# Motherboard_Connection.net
KiCad netlist of a schematic drawn in Altium Designer
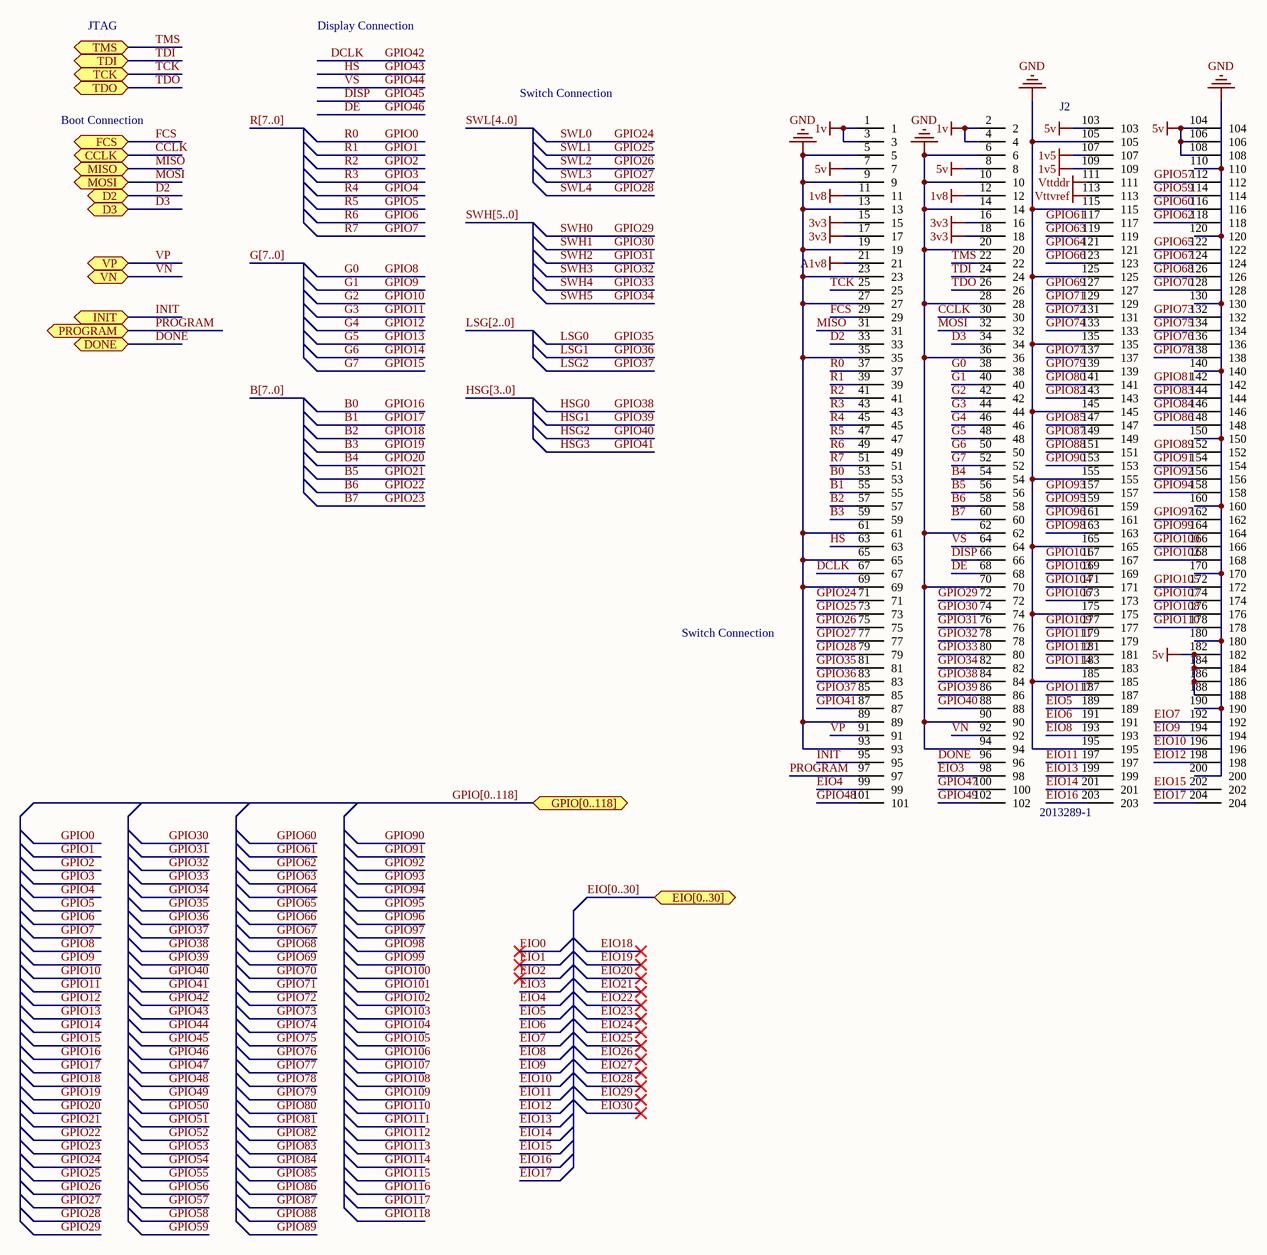
[diagram p0: Motherboard Connection.SchDoc]

(export (version "E")
  (design (tool "Eeschema 10.0.6"))
  (components
    (comp (ref "J2")
      (value "2013289-1")
      (footprint "DDR3 SODIMM Gold Finger")
      (description "204 Position 0.6 mm Pitch Right Angle Surface Mount Socket DIMM Connector")
      (fields (field (name "DIGI-KEY_PART_NUMBER") "A115021-ND") (field (name "MF") "TE Connectivity"))
      (libsource (lib "2020-09-26_17-27-19") (part "2013289-1"))
    )
  )
  (nets
    (net (code "2") (name "/CCLK") (class "Default")
      (node (ref "J2") (pin "30") (pinfunction "30_30") (pintype "passive"))
    )
    (net (code "3") (name "/D2") (class "Default")
      (node (ref "J2") (pin "33") (pinfunction "33_33") (pintype "passive"))
    )
    (net (code "4") (name "/D3") (class "Default")
      (node (ref "J2") (pin "34") (pinfunction "34_34") (pintype "passive"))
    )
    (net (code "5") (name "/DONE") (class "Default")
      (node (ref "J2") (pin "96") (pinfunction "96_96") (pintype "passive"))
    )
    (net (code "9") (name "/EIO3") (class "Default")
      (node (ref "J2") (pin "98") (pinfunction "98_98") (pintype "passive"))
    )
    (net (code "10") (name "/EIO4") (class "Default")
      (node (ref "J2") (pin "99") (pinfunction "99_99") (pintype "passive"))
    )
    (net (code "11") (name "/EIO5") (class "Default")
      (node (ref "J2") (pin "189") (pinfunction "189_189") (pintype "passive"))
    )
    (net (code "12") (name "/EIO6") (class "Default")
      (node (ref "J2") (pin "191") (pinfunction "191_191") (pintype "passive"))
    )
    (net (code "13") (name "/EIO7") (class "Default")
      (node (ref "J2") (pin "192") (pinfunction "192_192") (pintype "passive"))
    )
    (net (code "14") (name "/EIO8") (class "Default")
      (node (ref "J2") (pin "193") (pinfunction "193_193") (pintype "passive"))
    )
    (net (code "15") (name "/EIO9") (class "Default")
      (node (ref "J2") (pin "194") (pinfunction "194_194") (pintype "passive"))
    )
    (net (code "16") (name "/EIO10") (class "Default")
      (node (ref "J2") (pin "196") (pinfunction "196_196") (pintype "passive"))
    )
    (net (code "17") (name "/EIO11") (class "Default")
      (node (ref "J2") (pin "197") (pinfunction "197_197") (pintype "passive"))
    )
    (net (code "18") (name "/EIO12") (class "Default")
      (node (ref "J2") (pin "198") (pinfunction "198_198") (pintype "passive"))
    )
    (net (code "19") (name "/EIO13") (class "Default")
      (node (ref "J2") (pin "199") (pinfunction "199_199") (pintype "passive"))
    )
    (net (code "20") (name "/EIO14") (class "Default")
      (node (ref "J2") (pin "201") (pinfunction "201_201") (pintype "passive"))
    )
    (net (code "21") (name "/EIO15") (class "Default")
      (node (ref "J2") (pin "202") (pinfunction "202_202") (pintype "passive"))
    )
    (net (code "22") (name "/EIO16") (class "Default")
      (node (ref "J2") (pin "203") (pinfunction "203_203") (pintype "passive"))
    )
    (net (code "23") (name "/EIO17") (class "Default")
      (node (ref "J2") (pin "204") (pinfunction "204_204") (pintype "passive"))
    )
    (net (code "38") (name "/FCS") (class "Default")
      (node (ref "J2") (pin "29") (pinfunction "29_29") (pintype "passive"))
    )
    (net (code "39") (name "/GPIO0") (class "Default")
      (node (ref "J2") (pin "37") (pinfunction "37_37") (pintype "passive"))
    )
    (net (code "40") (name "/GPIO1") (class "Default")
      (node (ref "J2") (pin "39") (pinfunction "39_39") (pintype "passive"))
    )
    (net (code "41") (name "/GPIO2") (class "Default")
      (node (ref "J2") (pin "41") (pinfunction "41_41") (pintype "passive"))
    )
    (net (code "42") (name "/GPIO3") (class "Default")
      (node (ref "J2") (pin "43") (pinfunction "43_43") (pintype "passive"))
    )
    (net (code "43") (name "/GPIO4") (class "Default")
      (node (ref "J2") (pin "45") (pinfunction "45_45") (pintype "passive"))
    )
    (net (code "44") (name "/GPIO5") (class "Default")
      (node (ref "J2") (pin "47") (pinfunction "47_47") (pintype "passive"))
    )
    (net (code "45") (name "/GPIO6") (class "Default")
      (node (ref "J2") (pin "49") (pinfunction "49_49") (pintype "passive"))
    )
    (net (code "46") (name "/GPIO7") (class "Default")
      (node (ref "J2") (pin "51") (pinfunction "51_51") (pintype "passive"))
    )
    (net (code "47") (name "/GPIO8") (class "Default")
      (node (ref "J2") (pin "38") (pinfunction "38_38") (pintype "passive"))
    )
    (net (code "48") (name "/GPIO9") (class "Default")
      (node (ref "J2") (pin "40") (pinfunction "40_40") (pintype "passive"))
    )
    (net (code "49") (name "/GPIO10") (class "Default")
      (node (ref "J2") (pin "42") (pinfunction "42_42") (pintype "passive"))
    )
    (net (code "50") (name "/GPIO11") (class "Default")
      (node (ref "J2") (pin "44") (pinfunction "44_44") (pintype "passive"))
    )
    (net (code "51") (name "/GPIO12") (class "Default")
      (node (ref "J2") (pin "46") (pinfunction "46_46") (pintype "passive"))
    )
    (net (code "52") (name "/GPIO13") (class "Default")
      (node (ref "J2") (pin "48") (pinfunction "48_48") (pintype "passive"))
    )
    (net (code "53") (name "/GPIO14") (class "Default")
      (node (ref "J2") (pin "50") (pinfunction "50_50") (pintype "passive"))
    )
    (net (code "54") (name "/GPIO15") (class "Default")
      (node (ref "J2") (pin "52") (pinfunction "52_52") (pintype "passive"))
    )
    (net (code "55") (name "/GPIO16") (class "Default")
      (node (ref "J2") (pin "53") (pinfunction "53_53") (pintype "passive"))
    )
    (net (code "56") (name "/GPIO17") (class "Default")
      (node (ref "J2") (pin "55") (pinfunction "55_55") (pintype "passive"))
    )
    (net (code "57") (name "/GPIO18") (class "Default")
      (node (ref "J2") (pin "57") (pinfunction "57_57") (pintype "passive"))
    )
    (net (code "58") (name "/GPIO19") (class "Default")
      (node (ref "J2") (pin "59") (pinfunction "59_59") (pintype "passive"))
    )
    (net (code "59") (name "/GPIO20") (class "Default")
      (node (ref "J2") (pin "54") (pinfunction "54_54") (pintype "passive"))
    )
    (net (code "60") (name "/GPIO21") (class "Default")
      (node (ref "J2") (pin "56") (pinfunction "56_56") (pintype "passive"))
    )
    (net (code "61") (name "/GPIO22") (class "Default")
      (node (ref "J2") (pin "58") (pinfunction "58_58") (pintype "passive"))
    )
    (net (code "62") (name "/GPIO23") (class "Default")
      (node (ref "J2") (pin "60") (pinfunction "60_60") (pintype "passive"))
    )
    (net (code "63") (name "/GPIO42") (class "Default")
      (node (ref "J2") (pin "67") (pinfunction "67_67") (pintype "passive"))
    )
    (net (code "64") (name "/GPIO43") (class "Default")
      (node (ref "J2") (pin "63") (pinfunction "63_63") (pintype "passive"))
    )
    (net (code "65") (name "/GPIO44") (class "Default")
      (node (ref "J2") (pin "64") (pinfunction "64_64") (pintype "passive"))
    )
    (net (code "66") (name "/GPIO45") (class "Default")
      (node (ref "J2") (pin "66") (pinfunction "66_66") (pintype "passive"))
    )
    (net (code "67") (name "/GPIO46") (class "Default")
      (node (ref "J2") (pin "68") (pinfunction "68_68") (pintype "passive"))
    )
    (net (code "68") (name "/GPIO47") (class "Default")
      (node (ref "J2") (pin "100") (pinfunction "100_100") (pintype "passive"))
    )
    (net (code "69") (name "/GPIO48") (class "Default")
      (node (ref "J2") (pin "101") (pinfunction "101_101") (pintype "passive"))
    )
    (net (code "70") (name "/GPIO49") (class "Default")
      (node (ref "J2") (pin "102") (pinfunction "102_102") (pintype "passive"))
    )
    (net (code "78") (name "/GPIO57") (class "Default")
      (node (ref "J2") (pin "112") (pinfunction "112_112") (pintype "passive"))
    )
    (net (code "80") (name "/GPIO59") (class "Default")
      (node (ref "J2") (pin "114") (pinfunction "114_114") (pintype "passive"))
    )
    (net (code "81") (name "/GPIO60") (class "Default")
      (node (ref "J2") (pin "116") (pinfunction "116_116") (pintype "passive"))
    )
    (net (code "82") (name "/GPIO61") (class "Default")
      (node (ref "J2") (pin "117") (pinfunction "117_117") (pintype "passive"))
    )
    (net (code "83") (name "/GPIO62") (class "Default")
      (node (ref "J2") (pin "118") (pinfunction "118_118") (pintype "passive"))
    )
    (net (code "84") (name "/GPIO63") (class "Default")
      (node (ref "J2") (pin "119") (pinfunction "119_119") (pintype "passive"))
    )
    (net (code "85") (name "/GPIO64") (class "Default")
      (node (ref "J2") (pin "121") (pinfunction "121_121") (pintype "passive"))
    )
    (net (code "86") (name "/GPIO65") (class "Default")
      (node (ref "J2") (pin "122") (pinfunction "122_122") (pintype "passive"))
    )
    (net (code "87") (name "/GPIO66") (class "Default")
      (node (ref "J2") (pin "123") (pinfunction "123_123") (pintype "passive"))
    )
    (net (code "88") (name "/GPIO67") (class "Default")
      (node (ref "J2") (pin "124") (pinfunction "124_124") (pintype "passive"))
    )
    (net (code "89") (name "/GPIO68") (class "Default")
      (node (ref "J2") (pin "126") (pinfunction "126_126") (pintype "passive"))
    )
    (net (code "90") (name "/GPIO69") (class "Default")
      (node (ref "J2") (pin "127") (pinfunction "127_127") (pintype "passive"))
    )
    (net (code "91") (name "/GPIO70") (class "Default")
      (node (ref "J2") (pin "128") (pinfunction "128_128") (pintype "passive"))
    )
    (net (code "92") (name "/GPIO71") (class "Default")
      (node (ref "J2") (pin "129") (pinfunction "129_129") (pintype "passive"))
    )
    (net (code "93") (name "/GPIO72") (class "Default")
      (node (ref "J2") (pin "131") (pinfunction "131_131") (pintype "passive"))
    )
    (net (code "94") (name "/GPIO73") (class "Default")
      (node (ref "J2") (pin "132") (pinfunction "132_132") (pintype "passive"))
    )
    (net (code "95") (name "/GPIO74") (class "Default")
      (node (ref "J2") (pin "133") (pinfunction "133_133") (pintype "passive"))
    )
    (net (code "96") (name "/GPIO75") (class "Default")
      (node (ref "J2") (pin "134") (pinfunction "134_134") (pintype "passive"))
    )
    (net (code "97") (name "/GPIO76") (class "Default")
      (node (ref "J2") (pin "136") (pinfunction "136_136") (pintype "passive"))
    )
    (net (code "98") (name "/GPIO77") (class "Default")
      (node (ref "J2") (pin "137") (pinfunction "137_137") (pintype "passive"))
    )
    (net (code "99") (name "/GPIO78") (class "Default")
      (node (ref "J2") (pin "138") (pinfunction "138_138") (pintype "passive"))
    )
    (net (code "100") (name "/GPIO79") (class "Default")
      (node (ref "J2") (pin "139") (pinfunction "139_139") (pintype "passive"))
    )
    (net (code "101") (name "/GPIO80") (class "Default")
      (node (ref "J2") (pin "141") (pinfunction "141_141") (pintype "passive"))
    )
    (net (code "102") (name "/GPIO81") (class "Default")
      (node (ref "J2") (pin "142") (pinfunction "142_142") (pintype "passive"))
    )
    (net (code "103") (name "/GPIO82") (class "Default")
      (node (ref "J2") (pin "143") (pinfunction "143_143") (pintype "passive"))
    )
    (net (code "104") (name "/GPIO83") (class "Default")
      (node (ref "J2") (pin "144") (pinfunction "144_144") (pintype "passive"))
    )
    (net (code "105") (name "/GPIO84") (class "Default")
      (node (ref "J2") (pin "146") (pinfunction "146_146") (pintype "passive"))
    )
    (net (code "106") (name "/GPIO85") (class "Default")
      (node (ref "J2") (pin "147") (pinfunction "147_147") (pintype "passive"))
    )
    (net (code "107") (name "/GPIO86") (class "Default")
      (node (ref "J2") (pin "148") (pinfunction "148_148") (pintype "passive"))
    )
    (net (code "108") (name "/GPIO87") (class "Default")
      (node (ref "J2") (pin "149") (pinfunction "149_149") (pintype "passive"))
    )
    (net (code "109") (name "/GPIO88") (class "Default")
      (node (ref "J2") (pin "151") (pinfunction "151_151") (pintype "passive"))
    )
    (net (code "110") (name "/GPIO89") (class "Default")
      (node (ref "J2") (pin "152") (pinfunction "152_152") (pintype "passive"))
    )
    (net (code "111") (name "/GPIO90") (class "Default")
      (node (ref "J2") (pin "153") (pinfunction "153_153") (pintype "passive"))
    )
    (net (code "112") (name "/GPIO91") (class "Default")
      (node (ref "J2") (pin "154") (pinfunction "154_154") (pintype "passive"))
    )
    (net (code "113") (name "/GPIO92") (class "Default")
      (node (ref "J2") (pin "156") (pinfunction "156_156") (pintype "passive"))
    )
    (net (code "114") (name "/GPIO93") (class "Default")
      (node (ref "J2") (pin "157") (pinfunction "157_157") (pintype "passive"))
    )
    (net (code "115") (name "/GPIO94") (class "Default")
      (node (ref "J2") (pin "158") (pinfunction "158_158") (pintype "passive"))
    )
    (net (code "116") (name "/GPIO95") (class "Default")
      (node (ref "J2") (pin "159") (pinfunction "159_159") (pintype "passive"))
    )
    (net (code "117") (name "/GPIO96") (class "Default")
      (node (ref "J2") (pin "161") (pinfunction "161_161") (pintype "passive"))
    )
    (net (code "118") (name "/GPIO97") (class "Default")
      (node (ref "J2") (pin "162") (pinfunction "162_162") (pintype "passive"))
    )
    (net (code "119") (name "/GPIO98") (class "Default")
      (node (ref "J2") (pin "163") (pinfunction "163_163") (pintype "passive"))
    )
    (net (code "120") (name "/GPIO99") (class "Default")
      (node (ref "J2") (pin "164") (pinfunction "164_164") (pintype "passive"))
    )
    (net (code "121") (name "/GPIO100") (class "Default")
      (node (ref "J2") (pin "166") (pinfunction "166_166") (pintype "passive"))
    )
    (net (code "122") (name "/GPIO101") (class "Default")
      (node (ref "J2") (pin "167") (pinfunction "167_167") (pintype "passive"))
    )
    (net (code "123") (name "/GPIO102") (class "Default")
      (node (ref "J2") (pin "168") (pinfunction "168_168") (pintype "passive"))
    )
    (net (code "124") (name "/GPIO103") (class "Default")
      (node (ref "J2") (pin "169") (pinfunction "169_169") (pintype "passive"))
    )
    (net (code "125") (name "/GPIO104") (class "Default")
      (node (ref "J2") (pin "171") (pinfunction "171_171") (pintype "passive"))
    )
    (net (code "126") (name "/GPIO105") (class "Default")
      (node (ref "J2") (pin "172") (pinfunction "172_172") (pintype "passive"))
    )
    (net (code "127") (name "/GPIO106") (class "Default")
      (node (ref "J2") (pin "173") (pinfunction "173_173") (pintype "passive"))
    )
    (net (code "128") (name "/GPIO107") (class "Default")
      (node (ref "J2") (pin "174") (pinfunction "174_174") (pintype "passive"))
    )
    (net (code "129") (name "/GPIO108") (class "Default")
      (node (ref "J2") (pin "176") (pinfunction "176_176") (pintype "passive"))
    )
    (net (code "130") (name "/GPIO109") (class "Default")
      (node (ref "J2") (pin "177") (pinfunction "177_177") (pintype "passive"))
    )
    (net (code "131") (name "/GPIO110") (class "Default")
      (node (ref "J2") (pin "178") (pinfunction "178_178") (pintype "passive"))
    )
    (net (code "132") (name "/GPIO111") (class "Default")
      (node (ref "J2") (pin "179") (pinfunction "179_179") (pintype "passive"))
    )
    (net (code "133") (name "/GPIO112") (class "Default")
      (node (ref "J2") (pin "181") (pinfunction "181_181") (pintype "passive"))
    )
    (net (code "135") (name "/GPIO114") (class "Default")
      (node (ref "J2") (pin "183") (pinfunction "183_183") (pintype "passive"))
    )
    (net (code "138") (name "/GPIO117") (class "Default")
      (node (ref "J2") (pin "187") (pinfunction "187_187") (pintype "passive"))
    )
    (net (code "142") (name "/HSG0") (class "Default")
      (node (ref "J2") (pin "84") (pinfunction "84_84") (pintype "passive"))
    )
    (net (code "143") (name "/HSG1") (class "Default")
      (node (ref "J2") (pin "86") (pinfunction "86_86") (pintype "passive"))
    )
    (net (code "144") (name "/HSG2") (class "Default")
      (node (ref "J2") (pin "88") (pinfunction "88_88") (pintype "passive"))
    )
    (net (code "145") (name "/HSG3") (class "Default")
      (node (ref "J2") (pin "87") (pinfunction "87_87") (pintype "passive"))
    )
    (net (code "147") (name "/INIT") (class "Default")
      (node (ref "J2") (pin "95") (pinfunction "95_95") (pintype "passive"))
    )
    (net (code "148") (name "/LSG0") (class "Default")
      (node (ref "J2") (pin "81") (pinfunction "81_81") (pintype "passive"))
    )
    (net (code "149") (name "/LSG1") (class "Default")
      (node (ref "J2") (pin "83") (pinfunction "83_83") (pintype "passive"))
    )
    (net (code "150") (name "/LSG2") (class "Default")
      (node (ref "J2") (pin "85") (pinfunction "85_85") (pintype "passive"))
    )
    (net (code "152") (name "/MISO") (class "Default")
      (node (ref "J2") (pin "31") (pinfunction "31_31") (pintype "passive"))
    )
    (net (code "153") (name "/MOSI") (class "Default")
      (node (ref "J2") (pin "32") (pinfunction "32_32") (pintype "passive"))
    )
    (net (code "154") (name "/PROGRAM") (class "Default")
      (node (ref "J2") (pin "97") (pinfunction "97_97") (pintype "passive"))
    )
    (net (code "156") (name "/SWH0") (class "Default")
      (node (ref "J2") (pin "72") (pinfunction "72_72") (pintype "passive"))
    )
    (net (code "157") (name "/SWH1") (class "Default")
      (node (ref "J2") (pin "74") (pinfunction "74_74") (pintype "passive"))
    )
    (net (code "158") (name "/SWH2") (class "Default")
      (node (ref "J2") (pin "76") (pinfunction "76_76") (pintype "passive"))
    )
    (net (code "159") (name "/SWH3") (class "Default")
      (node (ref "J2") (pin "78") (pinfunction "78_78") (pintype "passive"))
    )
    (net (code "160") (name "/SWH4") (class "Default")
      (node (ref "J2") (pin "80") (pinfunction "80_80") (pintype "passive"))
    )
    (net (code "161") (name "/SWH5") (class "Default")
      (node (ref "J2") (pin "82") (pinfunction "82_82") (pintype "passive"))
    )
    (net (code "163") (name "/SWL0") (class "Default")
      (node (ref "J2") (pin "71") (pinfunction "71_71") (pintype "passive"))
    )
    (net (code "164") (name "/SWL1") (class "Default")
      (node (ref "J2") (pin "73") (pinfunction "73_73") (pintype "passive"))
    )
    (net (code "165") (name "/SWL2") (class "Default")
      (node (ref "J2") (pin "75") (pinfunction "75_75") (pintype "passive"))
    )
    (net (code "166") (name "/SWL3") (class "Default")
      (node (ref "J2") (pin "77") (pinfunction "77_77") (pintype "passive"))
    )
    (net (code "167") (name "/SWL4") (class "Default")
      (node (ref "J2") (pin "79") (pinfunction "79_79") (pintype "passive"))
    )
    (net (code "169") (name "/TCK") (class "Default")
      (node (ref "J2") (pin "25") (pinfunction "25_25") (pintype "passive"))
    )
    (net (code "170") (name "/TDI") (class "Default")
      (node (ref "J2") (pin "24") (pinfunction "24_24") (pintype "passive"))
    )
    (net (code "171") (name "/TDO") (class "Default")
      (node (ref "J2") (pin "26") (pinfunction "26_26") (pintype "passive"))
    )
    (net (code "172") (name "/TMS") (class "Default")
      (node (ref "J2") (pin "22") (pinfunction "22_22") (pintype "passive"))
    )
    (net (code "173") (name "/VN") (class "Default")
      (node (ref "J2") (pin "92") (pinfunction "92_92") (pintype "passive"))
    )
    (net (code "174") (name "/VP") (class "Default")
      (node (ref "J2") (pin "91") (pinfunction "91_91") (pintype "passive"))
    )
    (net (code "175") (name "1v") (class "Default")
      (node (ref "J2") (pin "1") (pinfunction "1_1") (pintype "passive"))
      (node (ref "J2") (pin "2") (pinfunction "2_2") (pintype "passive"))
      (node (ref "J2") (pin "3") (pinfunction "3_3") (pintype "passive"))
      (node (ref "J2") (pin "4") (pinfunction "4_4") (pintype "passive"))
    )
    (net (code "176") (name "1v5") (class "Default")
      (node (ref "J2") (pin "107") (pinfunction "107_107") (pintype "passive"))
      (node (ref "J2") (pin "109") (pinfunction "109_109") (pintype "passive"))
    )
    (net (code "177") (name "1v8") (class "Default")
      (node (ref "J2") (pin "11") (pinfunction "11_11") (pintype "passive"))
      (node (ref "J2") (pin "12") (pinfunction "12_12") (pintype "passive"))
    )
    (net (code "178") (name "3v3") (class "Default")
      (node (ref "J2") (pin "15") (pinfunction "15_15") (pintype "passive"))
      (node (ref "J2") (pin "16") (pinfunction "16_16") (pintype "passive"))
      (node (ref "J2") (pin "17") (pinfunction "17_17") (pintype "passive"))
      (node (ref "J2") (pin "18") (pinfunction "18_18") (pintype "passive"))
    )
    (net (code "179") (name "5v") (class "Default")
      (node (ref "J2") (pin "103") (pinfunction "103_103") (pintype "passive"))
      (node (ref "J2") (pin "104") (pinfunction "104_104") (pintype "passive"))
      (node (ref "J2") (pin "106") (pinfunction "106_106") (pintype "passive"))
      (node (ref "J2") (pin "108") (pinfunction "108_108") (pintype "passive"))
      (node (ref "J2") (pin "182") (pinfunction "182_182") (pintype "passive"))
      (node (ref "J2") (pin "184") (pinfunction "184_184") (pintype "passive"))
      (node (ref "J2") (pin "186") (pinfunction "186_186") (pintype "passive"))
      (node (ref "J2") (pin "188") (pinfunction "188_188") (pintype "passive"))
      (node (ref "J2") (pin "7") (pinfunction "7_7") (pintype "passive"))
      (node (ref "J2") (pin "8") (pinfunction "8_8") (pintype "passive"))
    )
    (net (code "180") (name "A1v8") (class "Default")
      (node (ref "J2") (pin "21") (pinfunction "21_21") (pintype "passive"))
    )
    (net (code "181") (name "GND") (class "Default")
      (node (ref "J2") (pin "10") (pinfunction "10_10") (pintype "passive"))
      (node (ref "J2") (pin "105") (pinfunction "105_105") (pintype "passive"))
      (node (ref "J2") (pin "110") (pinfunction "110_110") (pintype "passive"))
      (node (ref "J2") (pin "115") (pinfunction "115_115") (pintype "passive"))
      (node (ref "J2") (pin "120") (pinfunction "120_120") (pintype "passive"))
      (node (ref "J2") (pin "125") (pinfunction "125_125") (pintype "passive"))
      (node (ref "J2") (pin "13") (pinfunction "13_13") (pintype "passive"))
      (node (ref "J2") (pin "130") (pinfunction "130_130") (pintype "passive"))
      (node (ref "J2") (pin "135") (pinfunction "135_135") (pintype "passive"))
      (node (ref "J2") (pin "14") (pinfunction "14_14") (pintype "passive"))
      (node (ref "J2") (pin "140") (pinfunction "140_140") (pintype "passive"))
      (node (ref "J2") (pin "145") (pinfunction "145_145") (pintype "passive"))
      (node (ref "J2") (pin "150") (pinfunction "150_150") (pintype "passive"))
      (node (ref "J2") (pin "155") (pinfunction "155_155") (pintype "passive"))
      (node (ref "J2") (pin "160") (pinfunction "160_160") (pintype "passive"))
      (node (ref "J2") (pin "165") (pinfunction "165_165") (pintype "passive"))
      (node (ref "J2") (pin "170") (pinfunction "170_170") (pintype "passive"))
      (node (ref "J2") (pin "175") (pinfunction "175_175") (pintype "passive"))
      (node (ref "J2") (pin "180") (pinfunction "180_180") (pintype "passive"))
      (node (ref "J2") (pin "185") (pinfunction "185_185") (pintype "passive"))
      (node (ref "J2") (pin "19") (pinfunction "19_19") (pintype "passive"))
      (node (ref "J2") (pin "190") (pinfunction "190_190") (pintype "passive"))
      (node (ref "J2") (pin "195") (pinfunction "195_195") (pintype "passive"))
      (node (ref "J2") (pin "20") (pinfunction "20_20") (pintype "passive"))
      (node (ref "J2") (pin "200") (pinfunction "200_200") (pintype "passive"))
      (node (ref "J2") (pin "23") (pinfunction "23_23") (pintype "passive"))
      (node (ref "J2") (pin "27") (pinfunction "27_27") (pintype "passive"))
      (node (ref "J2") (pin "28") (pinfunction "28_28") (pintype "passive"))
      (node (ref "J2") (pin "35") (pinfunction "35_35") (pintype "passive"))
      (node (ref "J2") (pin "36") (pinfunction "36_36") (pintype "passive"))
      (node (ref "J2") (pin "5") (pinfunction "5_5") (pintype "passive"))
      (node (ref "J2") (pin "6") (pinfunction "6_6") (pintype "passive"))
      (node (ref "J2") (pin "61") (pinfunction "61_61") (pintype "passive"))
      (node (ref "J2") (pin "62") (pinfunction "62_62") (pintype "passive"))
      (node (ref "J2") (pin "65") (pinfunction "65_65") (pintype "passive"))
      (node (ref "J2") (pin "69") (pinfunction "69_69") (pintype "passive"))
      (node (ref "J2") (pin "70") (pinfunction "70_70") (pintype "passive"))
      (node (ref "J2") (pin "89") (pinfunction "89_89") (pintype "passive"))
      (node (ref "J2") (pin "9") (pinfunction "9_9") (pintype "passive"))
      (node (ref "J2") (pin "90") (pinfunction "90_90") (pintype "passive"))
      (node (ref "J2") (pin "93") (pinfunction "93_93") (pintype "passive"))
      (node (ref "J2") (pin "94") (pinfunction "94_94") (pintype "passive"))
    )
    (net (code "182") (name "Vttddr") (class "Default")
      (node (ref "J2") (pin "111") (pinfunction "111_111") (pintype "passive"))
    )
    (net (code "183") (name "Vttvref") (class "Default")
      (node (ref "J2") (pin "113") (pinfunction "113_113") (pintype "passive"))
    )
  )
)
